# PicKit2_-_v4550.net
KiCad netlist of a schematic drawn in EAGLE
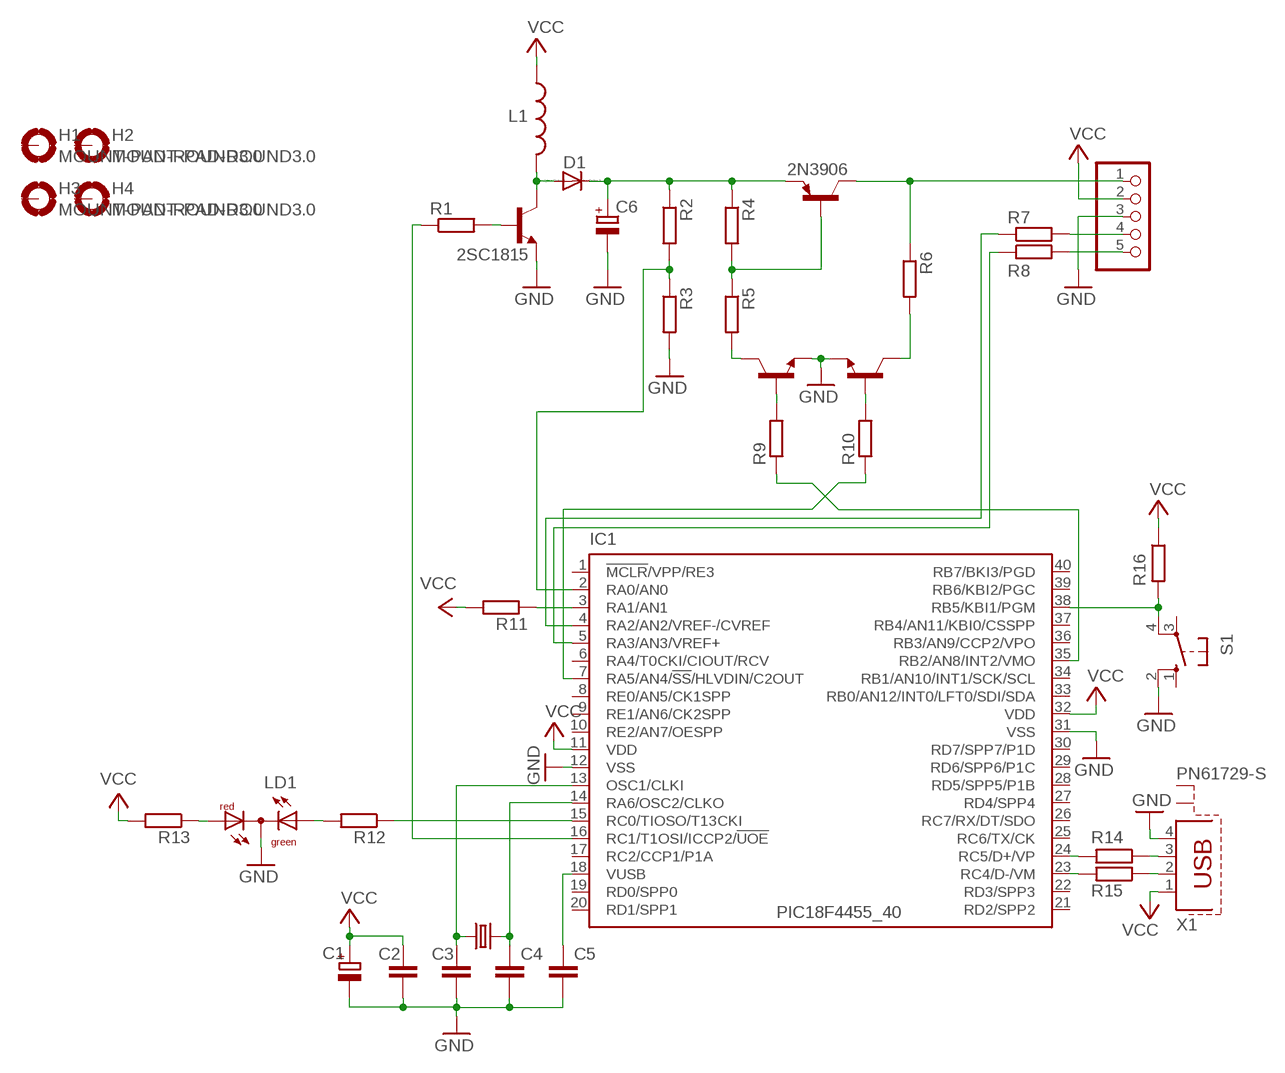
[diagram p0: schematic, sheet 1]

(export (version "E")
  (design (tool "Eeschema 10.0.6"))
  (components
    (comp (ref "C1")
      (value "CPOL-EUE2,5-6E")
      (footprint "eagle-import:E2,5-6E")
      (libsource (lib "eagle-import") (part "CPOL-EUE2,5-6E"))
    )
    (comp (ref "C2")
      (value "C-EU050-025X075")
      (footprint "eagle-import:C050-025X075")
      (libsource (lib "eagle-import") (part "C-EU050-025X075"))
    )
    (comp (ref "C3")
      (value "C-EU050-025X075")
      (footprint "eagle-import:C050-025X075")
      (libsource (lib "eagle-import") (part "C-EU050-025X075"))
    )
    (comp (ref "C4")
      (value "C-EU050-025X075")
      (footprint "eagle-import:C050-025X075")
      (libsource (lib "eagle-import") (part "C-EU050-025X075"))
    )
    (comp (ref "C5")
      (value "C-EU050-025X075")
      (footprint "eagle-import:C050-025X075")
      (libsource (lib "eagle-import") (part "C-EU050-025X075"))
    )
    (comp (ref "C6")
      (value "CPOL-EUE2,5-6E")
      (footprint "eagle-import:E2,5-6E")
      (libsource (lib "eagle-import") (part "CPOL-EUE2,5-6E"))
    )
    (comp (ref "D1")
      (value "1N4148DO35-10")
      (footprint "eagle-import:DO35-10")
      (libsource (lib "eagle-import") (part "1N4148DO35-10"))
    )
    (comp (ref "H1")
      (value "MOUNT-PAD-ROUND3.0")
      (footprint "eagle-import:3,0-PAD")
      (libsource (lib "eagle-import") (part "MOUNT-PAD-ROUND3.0"))
    )
    (comp (ref "H2")
      (value "MOUNT-PAD-ROUND3.0")
      (footprint "eagle-import:3,0-PAD")
      (libsource (lib "eagle-import") (part "MOUNT-PAD-ROUND3.0"))
    )
    (comp (ref "H3")
      (value "MOUNT-PAD-ROUND3.0")
      (footprint "eagle-import:3,0-PAD")
      (libsource (lib "eagle-import") (part "MOUNT-PAD-ROUND3.0"))
    )
    (comp (ref "H4")
      (value "MOUNT-PAD-ROUND3.0")
      (footprint "eagle-import:3,0-PAD")
      (libsource (lib "eagle-import") (part "MOUNT-PAD-ROUND3.0"))
    )
    (comp (ref "IC1")
      (value "PIC18F4455_40")
      (footprint "eagle-import:DIL40")
      (fields (field (name "MF") "MICROCHIP") (field (name "MPN") "PIC18F4455-I/P"))
      (libsource (lib "eagle-import") (part "PIC18F4_40455"))
    )
    (comp (ref "JP1")
      (value "PINHD-1X5/90")
      (footprint "eagle-import:1X05_90")
      (libsource (lib "eagle-import") (part "PINHD-1X5/90"))
    )
    (comp (ref "L1")
      (value "L-USIR-2")
      (footprint "eagle-import:IR-2")
      (libsource (lib "eagle-import") (part "L-USIR-2"))
    )
    (comp (ref "LD1")
      (value "DUOLED-RG-C")
      (footprint "eagle-import:DUOLED-C-5MM")
      (libsource (lib "eagle-import") (part "DUOLED-RG-C"))
    )
    (comp (ref "Q1")
      (value "2N3906")
      (footprint "eagle-import:TO92")
      (libsource (lib "eagle-import") (part "2N3906"))
    )
    (comp (ref "R1")
      (value "R-EU_0207/10")
      (footprint "eagle-import:0207_10")
      (libsource (lib "eagle-import") (part "R-EU_0207/10"))
    )
    (comp (ref "R2")
      (value "R-EU_0207/10")
      (footprint "eagle-import:0207_10")
      (libsource (lib "eagle-import") (part "R-EU_0207/10"))
    )
    (comp (ref "R3")
      (value "R-EU_0207/10")
      (footprint "eagle-import:0207_10")
      (libsource (lib "eagle-import") (part "R-EU_0207/10"))
    )
    (comp (ref "R4")
      (value "R-EU_0207/10")
      (footprint "eagle-import:0207_10")
      (libsource (lib "eagle-import") (part "R-EU_0207/10"))
    )
    (comp (ref "R5")
      (value "R-EU_0207/10")
      (footprint "eagle-import:0207_10")
      (libsource (lib "eagle-import") (part "R-EU_0207/10"))
    )
    (comp (ref "R6")
      (value "R-EU_0207/10")
      (footprint "eagle-import:0207_10")
      (libsource (lib "eagle-import") (part "R-EU_0207/10"))
    )
    (comp (ref "R7")
      (value "R-EU_0207/10")
      (footprint "eagle-import:0207_10")
      (libsource (lib "eagle-import") (part "R-EU_0207/10"))
    )
    (comp (ref "R8")
      (value "R-EU_0207/10")
      (footprint "eagle-import:0207_10")
      (libsource (lib "eagle-import") (part "R-EU_0207/10"))
    )
    (comp (ref "R9")
      (value "R-EU_0207/10")
      (footprint "eagle-import:0207_10")
      (libsource (lib "eagle-import") (part "R-EU_0207/10"))
    )
    (comp (ref "R10")
      (value "R-EU_0207/10")
      (footprint "eagle-import:0207_10")
      (libsource (lib "eagle-import") (part "R-EU_0207/10"))
    )
    (comp (ref "R11")
      (value "R-EU_0207/10")
      (footprint "eagle-import:0207_10")
      (libsource (lib "eagle-import") (part "R-EU_0207/10"))
    )
    (comp (ref "R12")
      (value "R-EU_0207/10")
      (footprint "eagle-import:0207_10")
      (libsource (lib "eagle-import") (part "R-EU_0207/10"))
    )
    (comp (ref "R13")
      (value "R-EU_0207/10")
      (footprint "eagle-import:0207_10")
      (libsource (lib "eagle-import") (part "R-EU_0207/10"))
    )
    (comp (ref "R14")
      (value "R-EU_0207/10")
      (footprint "eagle-import:0207_10")
      (libsource (lib "eagle-import") (part "R-EU_0207/10"))
    )
    (comp (ref "R15")
      (value "R-EU_0207/10")
      (footprint "eagle-import:0207_10")
      (libsource (lib "eagle-import") (part "R-EU_0207/10"))
    )
    (comp (ref "R16")
      (value "R-EU_0207/10")
      (footprint "eagle-import:0207_10")
      (libsource (lib "eagle-import") (part "R-EU_0207/10"))
    )
    (comp (ref "S1")
      (value "10-XX")
      (footprint "eagle-import:B3F-10XX")
      (fields (field (name "MPN") "B3F-1000"))
      (libsource (lib "eagle-import") (part "10-XX"))
    )
    (comp (ref "T1")
      (value "2SC1815")
      (footprint "eagle-import:TO92-ECB")
      (libsource (lib "eagle-import") (part "2SC1815"))
    )
    (comp (ref "T2")
      (value "2SC1815")
      (footprint "eagle-import:TO92-ECB")
      (libsource (lib "eagle-import") (part "2SC1815"))
    )
    (comp (ref "T3")
      (value "2SC1815")
      (footprint "eagle-import:TO92-ECB")
      (libsource (lib "eagle-import") (part "2SC1815"))
    )
    (comp (ref "X1")
      (value "PN61729-S")
      (footprint "eagle-import:PN61729-S")
      (libsource (lib "eagle-import") (part "PN61729-S"))
    )
    (comp (ref "Y1")
      (value "CRYSTALHC49S")
      (footprint "eagle-import:HC49_S")
      (libsource (lib "eagle-import") (part "CRYSTALHC49S"))
    )
  )
  (nets
    (net (code "1") (name "GND") (class "Default")
      (node (ref "C1") (pin "-") (pinfunction "-_-") (pintype "passive"))
      (node (ref "C2") (pin "2") (pinfunction "2_2") (pintype "passive"))
      (node (ref "C3") (pin "2") (pinfunction "2_2") (pintype "passive"))
      (node (ref "C4") (pin "2") (pinfunction "2_2") (pintype "passive"))
      (node (ref "C5") (pin "2") (pinfunction "2_2") (pintype "passive"))
      (node (ref "C6") (pin "-") (pinfunction "-_-") (pintype "passive"))
      (node (ref "IC1") (pin "12") (pinfunction "VSS_12") (pintype "power_in"))
      (node (ref "IC1") (pin "31") (pinfunction "VSS_31") (pintype "power_in"))
      (node (ref "JP1") (pin "3") (pinfunction "3_3") (pintype "passive"))
      (node (ref "LD1") (pin "C") (pinfunction "C_C") (pintype "passive"))
      (node (ref "R3") (pin "2") (pinfunction "2_2") (pintype "passive"))
      (node (ref "S1") (pin "2") (pinfunction "S1_2") (pintype "passive"))
      (node (ref "T1") (pin "E") (pinfunction "E_E") (pintype "passive"))
      (node (ref "T2") (pin "E") (pinfunction "E_E") (pintype "passive"))
      (node (ref "T3") (pin "E") (pinfunction "E_E") (pintype "passive"))
      (node (ref "X1") (pin "4") (pinfunction "4_4") (pintype "passive"))
    )
    (net (code "2") (name "Net-(D1-PadA)") (class "Default")
      (node (ref "D1") (pin "A") (pinfunction "A_A") (pintype "passive"))
      (node (ref "L1") (pin "2") (pinfunction "2_2") (pintype "passive"))
      (node (ref "T1") (pin "C") (pinfunction "C_C") (pintype "passive"))
    )
    (net (code "3") (name "Net-(IC1-OSC1{slash}CLKI)") (class "Default")
      (node (ref "C3") (pin "1") (pinfunction "1_1") (pintype "passive"))
      (node (ref "IC1") (pin "13") (pinfunction "OSC1/CLKI_13") (pintype "input"))
      (node (ref "Y1") (pin "1") (pinfunction "1_1") (pintype "passive"))
    )
    (net (code "4") (name "Net-(IC1-RA0{slash}AN0)") (class "Default")
      (node (ref "IC1") (pin "2") (pinfunction "RA0/AN0_2") (pintype "bidirectional"))
      (node (ref "R2") (pin "2") (pinfunction "2_2") (pintype "passive"))
      (node (ref "R3") (pin "1") (pinfunction "1_1") (pintype "passive"))
    )
    (net (code "5") (name "Net-(IC1-RA1{slash}AN1)") (class "Default")
      (node (ref "IC1") (pin "3") (pinfunction "RA1/AN1_3") (pintype "bidirectional"))
      (node (ref "R11") (pin "1") (pinfunction "1_1") (pintype "passive"))
    )
    (net (code "6") (name "Net-(IC1-RA2{slash}AN2{slash}VREF-{slash}CVREF)") (class "Default")
      (node (ref "IC1") (pin "4") (pinfunction "RA2/AN2/VREF-/CVREF_4") (pintype "bidirectional"))
      (node (ref "R7") (pin "1") (pinfunction "1_1") (pintype "passive"))
    )
    (net (code "7") (name "Net-(IC1-RA3{slash}AN3{slash}VREF+)") (class "Default")
      (node (ref "IC1") (pin "5") (pinfunction "RA3/AN3/VREF+_5") (pintype "bidirectional"))
      (node (ref "R8") (pin "1") (pinfunction "1_1") (pintype "passive"))
    )
    (net (code "8") (name "Net-(IC1-RA5{slash}AN4{slash}~{SS}{slash}HLVDIN{slash}C2OUT)") (class "Default")
      (node (ref "IC1") (pin "7") (pinfunction "RA5/AN4/~{SS}/HLVDIN/C2OUT_7") (pintype "bidirectional"))
      (node (ref "R10") (pin "1") (pinfunction "1_1") (pintype "passive"))
    )
    (net (code "9") (name "Net-(IC1-RA6{slash}OSC2{slash}CLKO)") (class "Default")
      (node (ref "C4") (pin "1") (pinfunction "1_1") (pintype "passive"))
      (node (ref "IC1") (pin "14") (pinfunction "RA6/OSC2/CLKO_14") (pintype "output"))
      (node (ref "Y1") (pin "2") (pinfunction "2_2") (pintype "passive"))
    )
    (net (code "10") (name "Net-(IC1-RB2{slash}AN8{slash}INT2{slash}VMO)") (class "Default")
      (node (ref "IC1") (pin "35") (pinfunction "RB2/AN8/INT2/VMO_35") (pintype "bidirectional"))
      (node (ref "R9") (pin "1") (pinfunction "1_1") (pintype "passive"))
    )
    (net (code "11") (name "Net-(IC1-RB5{slash}KBI1{slash}PGM)") (class "Default")
      (node (ref "IC1") (pin "38") (pinfunction "RB5/KBI1/PGM_38") (pintype "bidirectional"))
      (node (ref "R16") (pin "2") (pinfunction "2_2") (pintype "passive"))
      (node (ref "S1") (pin "4") (pinfunction "P1_4") (pintype "passive"))
    )
    (net (code "12") (name "Net-(IC1-RC0{slash}TIOSO{slash}T13CKI)") (class "Default")
      (node (ref "IC1") (pin "15") (pinfunction "RC0/TIOSO/T13CKI_15") (pintype "bidirectional"))
      (node (ref "R12") (pin "1") (pinfunction "1_1") (pintype "passive"))
    )
    (net (code "13") (name "Net-(IC1-RC1{slash}T1OSI{slash}ICCP2{slash}~{UOE})") (class "Default")
      (node (ref "IC1") (pin "16") (pinfunction "RC1/T1OSI/ICCP2/~{UOE}_16") (pintype "bidirectional"))
      (node (ref "R1") (pin "1") (pinfunction "1_1") (pintype "passive"))
    )
    (net (code "14") (name "Net-(IC1-RC4{slash}D-{slash}VM)") (class "Default")
      (node (ref "IC1") (pin "23") (pinfunction "RC4/D-/VM_23") (pintype "bidirectional"))
      (node (ref "R15") (pin "2") (pinfunction "2_2") (pintype "passive"))
    )
    (net (code "15") (name "Net-(IC1-RC5{slash}D+{slash}VP)") (class "Default")
      (node (ref "IC1") (pin "24") (pinfunction "RC5/D+/VP_24") (pintype "bidirectional"))
      (node (ref "R14") (pin "2") (pinfunction "2_2") (pintype "passive"))
    )
    (net (code "16") (name "Net-(IC1-VUSB)") (class "Default")
      (node (ref "C5") (pin "1") (pinfunction "1_1") (pintype "passive"))
      (node (ref "IC1") (pin "18") (pinfunction "VUSB_18") (pintype "bidirectional"))
    )
    (net (code "17") (name "Net-(JP1-Pad4)") (class "Default")
      (node (ref "JP1") (pin "4") (pinfunction "4_4") (pintype "passive"))
      (node (ref "R7") (pin "2") (pinfunction "2_2") (pintype "passive"))
    )
    (net (code "18") (name "Net-(JP1-Pad5)") (class "Default")
      (node (ref "JP1") (pin "5") (pinfunction "5_5") (pintype "passive"))
      (node (ref "R8") (pin "2") (pinfunction "2_2") (pintype "passive"))
    )
    (net (code "19") (name "Net-(LD1-AG)") (class "Default")
      (node (ref "LD1") (pin "AX") (pinfunction "AG_AX") (pintype "passive"))
      (node (ref "R12") (pin "2") (pinfunction "2_2") (pintype "passive"))
    )
    (net (code "20") (name "Net-(LD1-PadAR)") (class "Default")
      (node (ref "LD1") (pin "AR") (pinfunction "AR_AR") (pintype "passive"))
      (node (ref "R13") (pin "1") (pinfunction "1_1") (pintype "passive"))
    )
    (net (code "21") (name "Net-(Q1-B)") (class "Default")
      (node (ref "Q1") (pin "2") (pinfunction "B_2") (pintype "passive"))
      (node (ref "R4") (pin "2") (pinfunction "2_2") (pintype "passive"))
      (node (ref "R5") (pin "1") (pinfunction "1_1") (pintype "passive"))
    )
    (net (code "22") (name "Net-(Q1-C)") (class "Default")
      (node (ref "JP1") (pin "1") (pinfunction "1_1") (pintype "passive"))
      (node (ref "Q1") (pin "1") (pinfunction "C_1") (pintype "passive"))
      (node (ref "R6") (pin "1") (pinfunction "1_1") (pintype "passive"))
    )
    (net (code "23") (name "Net-(Q1-E)") (class "Default")
      (node (ref "C6") (pin "+") (pinfunction "+_+") (pintype "passive"))
      (node (ref "D1") (pin "C") (pinfunction "C_C") (pintype "passive"))
      (node (ref "Q1") (pin "3") (pinfunction "E_3") (pintype "passive"))
      (node (ref "R2") (pin "1") (pinfunction "1_1") (pintype "passive"))
      (node (ref "R4") (pin "1") (pinfunction "1_1") (pintype "passive"))
    )
    (net (code "24") (name "Net-(R1-Pad2)") (class "Default")
      (node (ref "R1") (pin "2") (pinfunction "2_2") (pintype "passive"))
      (node (ref "T1") (pin "B") (pinfunction "B_B") (pintype "passive"))
    )
    (net (code "25") (name "Net-(R5-Pad2)") (class "Default")
      (node (ref "R5") (pin "2") (pinfunction "2_2") (pintype "passive"))
      (node (ref "T2") (pin "C") (pinfunction "C_C") (pintype "passive"))
    )
    (net (code "26") (name "Net-(R6-Pad2)") (class "Default")
      (node (ref "R6") (pin "2") (pinfunction "2_2") (pintype "passive"))
      (node (ref "T3") (pin "C") (pinfunction "C_C") (pintype "passive"))
    )
    (net (code "27") (name "Net-(R9-Pad2)") (class "Default")
      (node (ref "R9") (pin "2") (pinfunction "2_2") (pintype "passive"))
      (node (ref "T2") (pin "B") (pinfunction "B_B") (pintype "passive"))
    )
    (net (code "28") (name "Net-(R10-Pad2)") (class "Default")
      (node (ref "R10") (pin "2") (pinfunction "2_2") (pintype "passive"))
      (node (ref "T3") (pin "B") (pinfunction "B_B") (pintype "passive"))
    )
    (net (code "29") (name "Net-(R14-Pad1)") (class "Default")
      (node (ref "R14") (pin "1") (pinfunction "1_1") (pintype "passive"))
      (node (ref "X1") (pin "3") (pinfunction "3_3") (pintype "passive"))
    )
    (net (code "30") (name "Net-(R15-Pad1)") (class "Default")
      (node (ref "R15") (pin "1") (pinfunction "1_1") (pintype "passive"))
      (node (ref "X1") (pin "2") (pinfunction "2_2") (pintype "passive"))
    )
    (net (code "31") (name "VCC") (class "Default")
      (node (ref "C1") (pin "+") (pinfunction "+_+") (pintype "passive"))
      (node (ref "C2") (pin "1") (pinfunction "1_1") (pintype "passive"))
      (node (ref "IC1") (pin "11") (pinfunction "VDD_11") (pintype "power_in"))
      (node (ref "IC1") (pin "32") (pinfunction "VDD_32") (pintype "power_in"))
      (node (ref "JP1") (pin "2") (pinfunction "2_2") (pintype "passive"))
      (node (ref "L1") (pin "1") (pinfunction "1_1") (pintype "passive"))
      (node (ref "R11") (pin "2") (pinfunction "2_2") (pintype "passive"))
      (node (ref "R13") (pin "2") (pinfunction "2_2") (pintype "passive"))
      (node (ref "R16") (pin "1") (pinfunction "1_1") (pintype "passive"))
      (node (ref "X1") (pin "1") (pinfunction "1_1") (pintype "passive"))
    )
    (net (code "32") (name "unconnected-(H1-MOUNT-PadB3,0)") (class "Default")
      (node (ref "H1") (pin "B3,0") (pinfunction "MOUNT_B3,0") (pintype "passive"))
    )
    (net (code "33") (name "unconnected-(H2-MOUNT-PadB3,0)") (class "Default")
      (node (ref "H2") (pin "B3,0") (pinfunction "MOUNT_B3,0") (pintype "passive"))
    )
    (net (code "34") (name "unconnected-(H3-MOUNT-PadB3,0)") (class "Default")
      (node (ref "H3") (pin "B3,0") (pinfunction "MOUNT_B3,0") (pintype "passive"))
    )
    (net (code "35") (name "unconnected-(H4-MOUNT-PadB3,0)") (class "Default")
      (node (ref "H4") (pin "B3,0") (pinfunction "MOUNT_B3,0") (pintype "passive"))
    )
    (net (code "36") (name "unconnected-(IC1-RA4{slash}T0CKI{slash}CIOUT{slash}RCV-Pad6)") (class "Default")
      (node (ref "IC1") (pin "6") (pinfunction "RA4/T0CKI/CIOUT/RCV_6") (pintype "bidirectional"))
    )
    (net (code "37") (name "unconnected-(IC1-RB0{slash}AN12{slash}INT0{slash}LFT0{slash}SDI{slash}SDA-Pad33)") (class "Default")
      (node (ref "IC1") (pin "33") (pinfunction "RB0/AN12/INT0/LFT0/SDI/SDA_33") (pintype "bidirectional"))
    )
    (net (code "38") (name "unconnected-(IC1-RB1{slash}AN10{slash}INT1{slash}SCK{slash}SCL-Pad34)") (class "Default")
      (node (ref "IC1") (pin "34") (pinfunction "RB1/AN10/INT1/SCK/SCL_34") (pintype "bidirectional"))
    )
    (net (code "39") (name "unconnected-(IC1-RB3{slash}AN9{slash}CCP2{slash}VPO-Pad36)") (class "Default")
      (node (ref "IC1") (pin "36") (pinfunction "RB3/AN9/CCP2/VPO_36") (pintype "bidirectional"))
    )
    (net (code "40") (name "unconnected-(IC1-RB4{slash}AN11{slash}KBI0{slash}CSSPP-Pad37)") (class "Default")
      (node (ref "IC1") (pin "37") (pinfunction "RB4/AN11/KBI0/CSSPP_37") (pintype "bidirectional"))
    )
    (net (code "41") (name "unconnected-(IC1-RB6{slash}KBI2{slash}PGC-Pad39)") (class "Default")
      (node (ref "IC1") (pin "39") (pinfunction "RB6/KBI2/PGC_39") (pintype "bidirectional"))
    )
    (net (code "42") (name "unconnected-(IC1-RB7{slash}BKI3{slash}PGD-Pad40)") (class "Default")
      (node (ref "IC1") (pin "40") (pinfunction "RB7/BKI3/PGD_40") (pintype "bidirectional"))
    )
    (net (code "43") (name "unconnected-(IC1-RC2{slash}CCP1{slash}P1A-Pad17)") (class "Default")
      (node (ref "IC1") (pin "17") (pinfunction "RC2/CCP1/P1A_17") (pintype "bidirectional"))
    )
    (net (code "44") (name "unconnected-(IC1-RC6{slash}TX{slash}CK-Pad25)") (class "Default")
      (node (ref "IC1") (pin "25") (pinfunction "RC6/TX/CK_25") (pintype "bidirectional"))
    )
    (net (code "45") (name "unconnected-(IC1-RC7{slash}RX{slash}DT{slash}SDO-Pad26)") (class "Default")
      (node (ref "IC1") (pin "26") (pinfunction "RC7/RX/DT/SDO_26") (pintype "bidirectional"))
    )
    (net (code "46") (name "unconnected-(IC1-RD0{slash}SPP0-Pad19)") (class "Default")
      (node (ref "IC1") (pin "19") (pinfunction "RD0/SPP0_19") (pintype "bidirectional"))
    )
    (net (code "47") (name "unconnected-(IC1-RD1{slash}SPP1-Pad20)") (class "Default")
      (node (ref "IC1") (pin "20") (pinfunction "RD1/SPP1_20") (pintype "bidirectional"))
    )
    (net (code "48") (name "unconnected-(IC1-RD2{slash}SPP2-Pad21)") (class "Default")
      (node (ref "IC1") (pin "21") (pinfunction "RD2/SPP2_21") (pintype "bidirectional"))
    )
    (net (code "49") (name "unconnected-(IC1-RD3{slash}SPP3-Pad22)") (class "Default")
      (node (ref "IC1") (pin "22") (pinfunction "RD3/SPP3_22") (pintype "bidirectional"))
    )
    (net (code "50") (name "unconnected-(IC1-RD4{slash}SPP4-Pad27)") (class "Default")
      (node (ref "IC1") (pin "27") (pinfunction "RD4/SPP4_27") (pintype "bidirectional"))
    )
    (net (code "51") (name "unconnected-(IC1-RD5{slash}SPP5{slash}P1B-Pad28)") (class "Default")
      (node (ref "IC1") (pin "28") (pinfunction "RD5/SPP5/P1B_28") (pintype "bidirectional"))
    )
    (net (code "52") (name "unconnected-(IC1-RD6{slash}SPP6{slash}P1C-Pad29)") (class "Default")
      (node (ref "IC1") (pin "29") (pinfunction "RD6/SPP6/P1C_29") (pintype "bidirectional"))
    )
    (net (code "53") (name "unconnected-(IC1-RD7{slash}SPP7{slash}P1D-Pad30)") (class "Default")
      (node (ref "IC1") (pin "30") (pinfunction "RD7/SPP7/P1D_30") (pintype "bidirectional"))
    )
    (net (code "54") (name "unconnected-(IC1-RE0{slash}AN5{slash}CK1SPP-Pad8)") (class "Default")
      (node (ref "IC1") (pin "8") (pinfunction "RE0/AN5/CK1SPP_8") (pintype "bidirectional"))
    )
    (net (code "55") (name "unconnected-(IC1-RE1{slash}AN6{slash}CK2SPP-Pad9)") (class "Default")
      (node (ref "IC1") (pin "9") (pinfunction "RE1/AN6/CK2SPP_9") (pintype "bidirectional"))
    )
    (net (code "56") (name "unconnected-(IC1-RE2{slash}AN7{slash}OESPP-Pad10)") (class "Default")
      (node (ref "IC1") (pin "10") (pinfunction "RE2/AN7/OESPP_10") (pintype "bidirectional"))
    )
    (net (code "57") (name "unconnected-(IC1-~{MCLR}{slash}VPP{slash}RE3-Pad1)") (class "Default")
      (node (ref "IC1") (pin "1") (pinfunction "~{MCLR}/VPP/RE3_1") (pintype "input"))
    )
    (net (code "58") (name "unconnected-(S1-P-Pad3)") (class "Default")
      (node (ref "S1") (pin "3") (pinfunction "P_3") (pintype "passive"))
    )
    (net (code "59") (name "unconnected-(S1-S-Pad1)") (class "Default")
      (node (ref "S1") (pin "1") (pinfunction "S_1") (pintype "passive"))
    )
    (net (code "60") (name "unconnected-(X1-PadS1)") (class "Default")
      (node (ref "X1") (pin "S1") (pinfunction "S1_S1") (pintype "passive"))
    )
    (net (code "61") (name "unconnected-(X1-PadS2)") (class "Default")
      (node (ref "X1") (pin "S2") (pinfunction "S2_S2") (pintype "passive"))
    )
  )
)
